# PCB_RTM_Loopback.net
KiCad netlist of a schematic drawn in Altium Designer
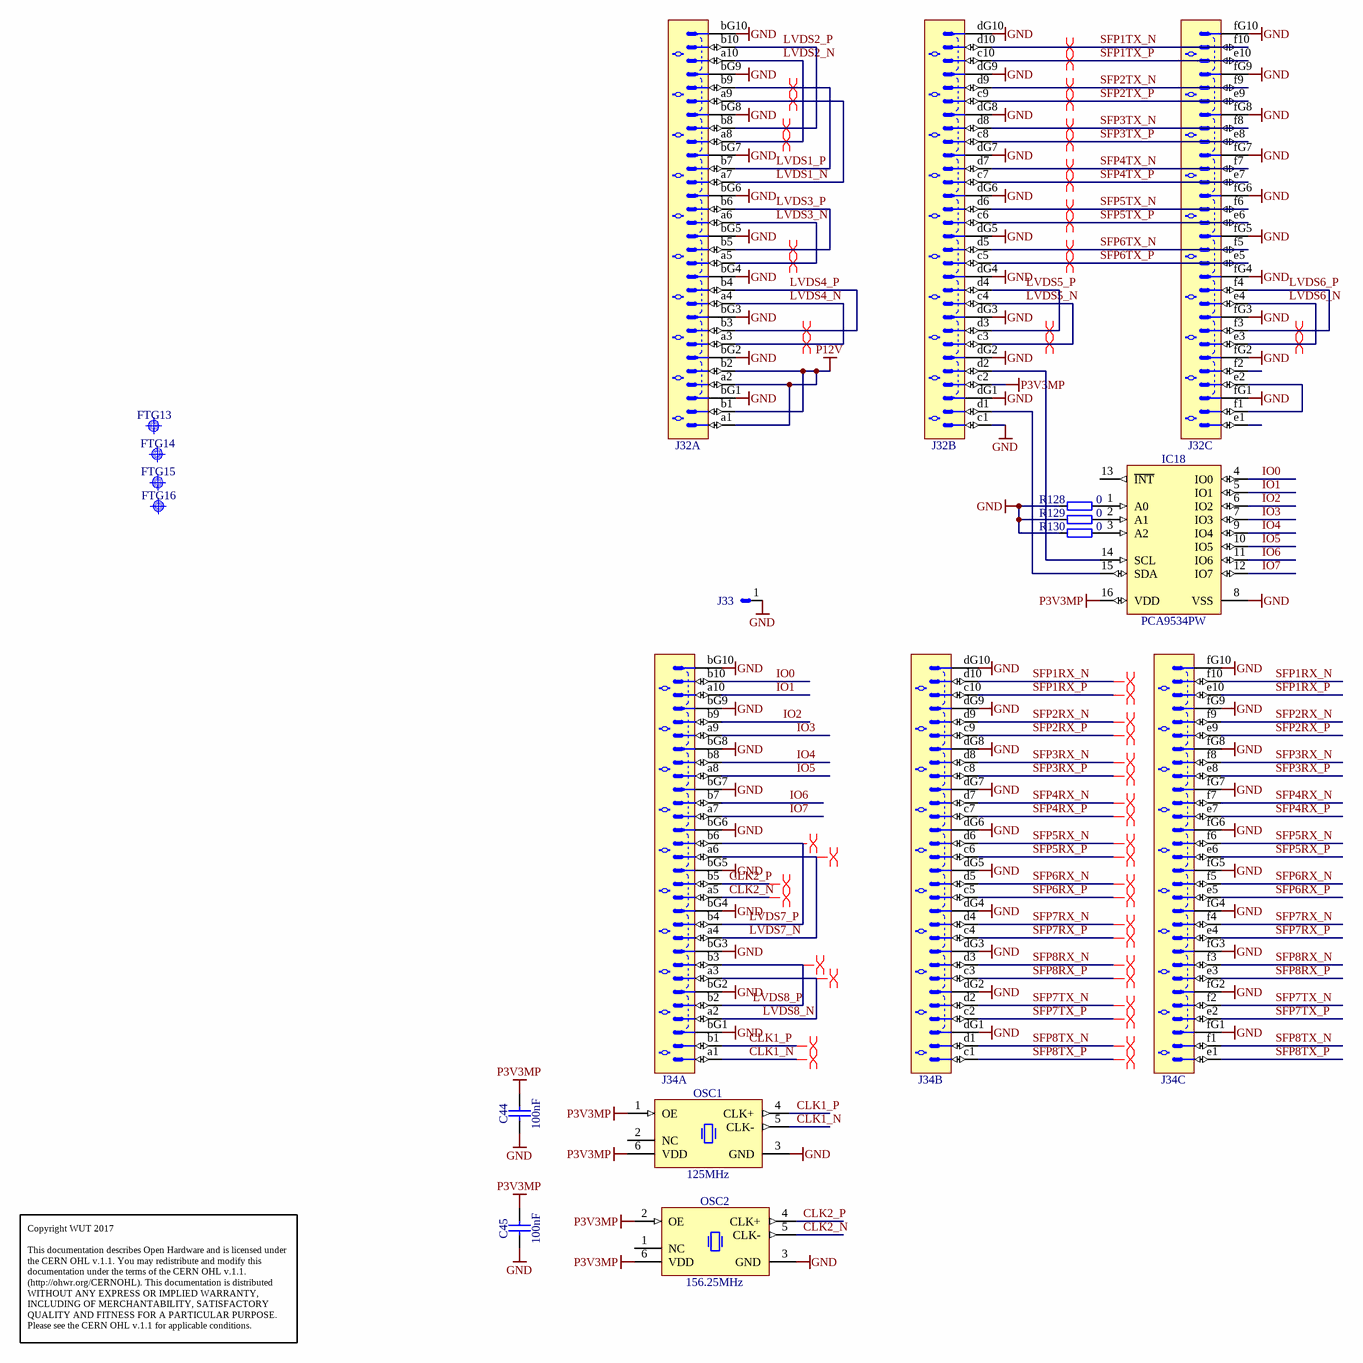
[diagram p0: PCB_RTM_Loopback.SchDoc]

(export (version "E")
  (design (tool "Eeschema 10.0.6"))
  (components
    (comp (ref "C44")
      (value "100nF")
      (footprint "CAPC1005X55N")
      (description "Non-polarised capacitor")
      (fields
        (field (name "PART NUMBER") "CC0402_100NF_16V_10%_X7R")
        (field (name "VOLTAGE") "16V")
        (field (name "AUTHOR") "CERN DEM JLC")
      )
      (libsource (lib "Capacitors") (part "Capacitor - non polarized"))
    )
    (comp (ref "C45")
      (value "100nF")
      (footprint "CAPC1005X55N")
      (description "Non-polarised capacitor")
      (fields
        (field (name "PART NUMBER") "CC0402_100NF_16V_10%_X7R")
        (field (name "VOLTAGE") "16V")
        (field (name "AUTHOR") "CERN DEM JLC")
      )
      (libsource (lib "Capacitors") (part "Capacitor - non polarized"))
    )
    (comp (ref "FTG13")
      (value "Use only in PCB")
      (footprint "FIDUCIAL_TOP_C100-200")
      (description "Fiducial Target")
      (fields (field (name "PART NUMBER") "FIDUCIAL_TARGET_C100-200") (field (name "AUTHOR") "CERN DEM JLC"))
      (libsource (lib "Eletro-mechanical") (part "Fiducial Target"))
    )
    (comp (ref "FTG14")
      (value "Use only in PCB")
      (footprint "FIDUCIAL_TOP_S100-200")
      (description "Fiducial Target")
      (fields (field (name "PART NUMBER") "FIDUCIAL_TARGET_S100-200") (field (name "AUTHOR") "CERN DEM JLC"))
      (libsource (lib "Eletro-mechanical") (part "Fiducial Target"))
    )
    (comp (ref "FTG15")
      (value "Use only in PCB")
      (footprint "FIDUCIAL_TOP_S200-400")
      (description "Fiducial Target")
      (fields (field (name "PART NUMBER") "FIDUCIAL_TARGET_S200-400") (field (name "AUTHOR") "CERN DEM JLC"))
      (libsource (lib "Eletro-mechanical") (part "Fiducial Target"))
    )
    (comp (ref "FTG16")
      (value "Use only in PCB")
      (footprint "FIDUCIAL_TOP_S100-200")
      (description "Fiducial Target")
      (fields (field (name "PART NUMBER") "FIDUCIAL_TARGET_S100-200") (field (name "AUTHOR") "CERN DEM JLC"))
      (libsource (lib "Eletro-mechanical") (part "Fiducial Target"))
    )
    (comp (ref "IC18")
      (value "PCA9534PW")
      (footprint "SOP65P640X110-16N")
      (description "8-Bit I2C-Bus and SMBus Low Power I/O Port with Interrupt")
      (fields (field (name "MANUFACTURER") "ANALOG DEVICES") (field (name "AUTHOR") "CERN DEM JLC"))
      (libsource (lib "ICs And Semiconductors") (part "PCA9534PW"))
    )
    (comp (ref "J32")
      (value "~")
      (footprint "TYCO_6469183-1")
      (description "Connector 60 ATCA Male 30 Pairs (60 Signals) + 3x10 Ground")
      (fields (field (name "PART NUMBER") "TYCO_6469183-1"))
      (libsource (lib "Connectors") (part "Connector ATCA 60+30 Male"))
    )
    (comp (ref "J33")
      (value "~")
      (footprint "TYCO_1469265-1")
      (description "Single Pin Male")
      (fields (field (name "PART NUMBER") "TYCO_1469265-1"))
      (libsource (lib "Connectors") (part "Single Pin Male"))
    )
    (comp (ref "J34")
      (value "~")
      (footprint "TYCO_6469183-1")
      (description "Connector 60 ATCA Male 30 Pairs (60 Signals) + 3x10 Ground")
      (fields (field (name "PART NUMBER") "TYCO_6469183-1"))
      (libsource (lib "Connectors") (part "Connector ATCA 60+30 Male"))
    )
    (comp (ref "OSC1")
      (value "125MHz")
      (footprint "OSC_SILICON-LAB_SI531")
      (description "10-1400MHz, Crystal Oscillator (XO), Si531 Series")
      (fields
        (field (name "PART NUMBER") "OSC_125MHZ_SILICON-LAB_531BC125M000DG")
        (field (name "MANUFACTURER") "SILICON LABS")
        (field (name "AUTHOR") "CERN DEM MR")
      )
      (libsource (lib "ICs And Semiconductors") (part "Oscillator SILICON-LAB_Si531"))
    )
    (comp (ref "OSC2")
      (value "156.25MHz")
      (footprint "OSC_SILICON-LAB_SI530")
      (description "10-1400MHz, Crystal Oscillator (XO), Si530 Series")
      (fields
        (field (name "PART NUMBER") "OSC_156.25MHZ_SILICON-LAB_530BC156M250DG")
        (field (name "MANUFACTURER") "SILICON LABS")
        (field (name "AUTHOR") "CERN DEM MR")
      )
      (libsource (lib "ICs And Semiconductors") (part "Oscillator SILICON-LAB_Si530_a"))
    )
    (comp (ref "R128")
      (value "0")
      (footprint "RESC1005X40N")
      (description "Resistor")
      (fields
        (field (name "PART NUMBER") "R0402_0R_JUMPER")
        (field (name "MANUFACTURER") "GENERIC")
        (field (name "AUTHOR") "CERN DEM JLC")
      )
      (libsource (lib "Resistors") (part "Resistor"))
    )
    (comp (ref "R129")
      (value "0")
      (footprint "RESC1005X40N")
      (description "Resistor")
      (fields
        (field (name "PART NUMBER") "R0402_0R_JUMPER")
        (field (name "MANUFACTURER") "GENERIC")
        (field (name "AUTHOR") "CERN DEM JLC")
      )
      (libsource (lib "Resistors") (part "Resistor"))
    )
    (comp (ref "R130")
      (value "0")
      (footprint "RESC1005X40N")
      (description "Resistor")
      (fields
        (field (name "PART NUMBER") "R0402_0R_JUMPER")
        (field (name "MANUFACTURER") "GENERIC")
        (field (name "AUTHOR") "CERN DEM JLC")
      )
      (libsource (lib "Resistors") (part "Resistor"))
    )
  )
  (nets
    (net (code "1") (name "/CLK1_N") (class "Default")
      (node (ref "J34") (pin "a1") (pinfunction "a1_a1") (pintype "bidirectional"))
      (node (ref "OSC1") (pin "5") (pinfunction "CLK-_5") (pintype "output"))
    )
    (net (code "2") (name "/CLK1_P") (class "Default")
      (node (ref "J34") (pin "b1") (pinfunction "b1_b1") (pintype "bidirectional"))
      (node (ref "OSC1") (pin "4") (pinfunction "CLK+_4") (pintype "output"))
    )
    (net (code "3") (name "/CLK2_N") (class "Default")
      (node (ref "J34") (pin "a5") (pinfunction "a5_a5") (pintype "bidirectional"))
      (node (ref "OSC2") (pin "5") (pinfunction "CLK-_5") (pintype "output"))
    )
    (net (code "4") (name "/CLK2_P") (class "Default")
      (node (ref "J34") (pin "b5") (pinfunction "b5_b5") (pintype "bidirectional"))
      (node (ref "OSC2") (pin "4") (pinfunction "CLK+_4") (pintype "output"))
    )
    (net (code "5") (name "/IO0") (class "Default")
      (node (ref "IC18") (pin "4") (pinfunction "IO0_4") (pintype "bidirectional"))
      (node (ref "J34") (pin "b10") (pinfunction "b10_b10") (pintype "bidirectional"))
    )
    (net (code "6") (name "/IO1") (class "Default")
      (node (ref "IC18") (pin "5") (pinfunction "IO1_5") (pintype "bidirectional"))
      (node (ref "J34") (pin "a10") (pinfunction "a10_a10") (pintype "bidirectional"))
    )
    (net (code "7") (name "/IO2") (class "Default")
      (node (ref "IC18") (pin "6") (pinfunction "IO2_6") (pintype "bidirectional"))
      (node (ref "J34") (pin "b9") (pinfunction "b9_b9") (pintype "bidirectional"))
    )
    (net (code "8") (name "/IO3") (class "Default")
      (node (ref "IC18") (pin "7") (pinfunction "IO3_7") (pintype "bidirectional"))
      (node (ref "J34") (pin "a9") (pinfunction "a9_a9") (pintype "bidirectional"))
    )
    (net (code "9") (name "/IO4") (class "Default")
      (node (ref "IC18") (pin "9") (pinfunction "IO4_9") (pintype "bidirectional"))
      (node (ref "J34") (pin "b8") (pinfunction "b8_b8") (pintype "bidirectional"))
    )
    (net (code "10") (name "/IO5") (class "Default")
      (node (ref "IC18") (pin "10") (pinfunction "IO5_10") (pintype "bidirectional"))
      (node (ref "J34") (pin "a8") (pinfunction "a8_a8") (pintype "bidirectional"))
    )
    (net (code "11") (name "/IO6") (class "Default")
      (node (ref "IC18") (pin "11") (pinfunction "IO6_11") (pintype "bidirectional"))
      (node (ref "J34") (pin "b7") (pinfunction "b7_b7") (pintype "bidirectional"))
    )
    (net (code "12") (name "/IO7") (class "Default")
      (node (ref "IC18") (pin "12") (pinfunction "IO7_12") (pintype "bidirectional"))
      (node (ref "J34") (pin "a7") (pinfunction "a7_a7") (pintype "bidirectional"))
    )
    (net (code "13") (name "/LVDS1_N") (class "Default")
      (node (ref "J32") (pin "a7") (pinfunction "a7_a7") (pintype "bidirectional"))
      (node (ref "J32") (pin "a9") (pinfunction "a9_a9") (pintype "bidirectional"))
    )
    (net (code "14") (name "/LVDS1_P") (class "Default")
      (node (ref "J32") (pin "b7") (pinfunction "b7_b7") (pintype "bidirectional"))
      (node (ref "J32") (pin "b9") (pinfunction "b9_b9") (pintype "bidirectional"))
    )
    (net (code "15") (name "/LVDS2_N") (class "Default")
      (node (ref "J32") (pin "a10") (pinfunction "a10_a10") (pintype "bidirectional"))
      (node (ref "J32") (pin "a8") (pinfunction "a8_a8") (pintype "bidirectional"))
    )
    (net (code "16") (name "/LVDS2_P") (class "Default")
      (node (ref "J32") (pin "b10") (pinfunction "b10_b10") (pintype "bidirectional"))
      (node (ref "J32") (pin "b8") (pinfunction "b8_b8") (pintype "bidirectional"))
    )
    (net (code "17") (name "/LVDS3_N") (class "Default")
      (node (ref "J32") (pin "a5") (pinfunction "a5_a5") (pintype "bidirectional"))
      (node (ref "J32") (pin "a6") (pinfunction "a6_a6") (pintype "bidirectional"))
    )
    (net (code "18") (name "/LVDS3_P") (class "Default")
      (node (ref "J32") (pin "b5") (pinfunction "b5_b5") (pintype "bidirectional"))
      (node (ref "J32") (pin "b6") (pinfunction "b6_b6") (pintype "bidirectional"))
    )
    (net (code "19") (name "/LVDS4_N") (class "Default")
      (node (ref "J32") (pin "a3") (pinfunction "a3_a3") (pintype "bidirectional"))
      (node (ref "J32") (pin "a4") (pinfunction "a4_a4") (pintype "bidirectional"))
    )
    (net (code "20") (name "/LVDS4_P") (class "Default")
      (node (ref "J32") (pin "b3") (pinfunction "b3_b3") (pintype "bidirectional"))
      (node (ref "J32") (pin "b4") (pinfunction "b4_b4") (pintype "bidirectional"))
    )
    (net (code "21") (name "/LVDS5_N") (class "Default")
      (node (ref "J32") (pin "c3") (pinfunction "c3_c3") (pintype "bidirectional"))
      (node (ref "J32") (pin "c4") (pinfunction "c4_c4") (pintype "bidirectional"))
    )
    (net (code "22") (name "/LVDS5_P") (class "Default")
      (node (ref "J32") (pin "d3") (pinfunction "d3_d3") (pintype "bidirectional"))
      (node (ref "J32") (pin "d4") (pinfunction "d4_d4") (pintype "bidirectional"))
    )
    (net (code "23") (name "/LVDS6_N") (class "Default")
      (node (ref "J32") (pin "e3") (pinfunction "e3_e3") (pintype "bidirectional"))
      (node (ref "J32") (pin "e4") (pinfunction "e4_e4") (pintype "bidirectional"))
    )
    (net (code "24") (name "/LVDS6_P") (class "Default")
      (node (ref "J32") (pin "f3") (pinfunction "f3_f3") (pintype "bidirectional"))
      (node (ref "J32") (pin "f4") (pinfunction "f4_f4") (pintype "bidirectional"))
    )
    (net (code "25") (name "/LVDS7_N") (class "Default")
      (node (ref "J34") (pin "a4") (pinfunction "a4_a4") (pintype "bidirectional"))
      (node (ref "J34") (pin "a6") (pinfunction "a6_a6") (pintype "bidirectional"))
    )
    (net (code "26") (name "/LVDS7_P") (class "Default")
      (node (ref "J34") (pin "b4") (pinfunction "b4_b4") (pintype "bidirectional"))
      (node (ref "J34") (pin "b6") (pinfunction "b6_b6") (pintype "bidirectional"))
    )
    (net (code "27") (name "/LVDS8_N") (class "Default")
      (node (ref "J34") (pin "a2") (pinfunction "a2_a2") (pintype "bidirectional"))
      (node (ref "J34") (pin "a3") (pinfunction "a3_a3") (pintype "bidirectional"))
    )
    (net (code "28") (name "/LVDS8_P") (class "Default")
      (node (ref "J34") (pin "b2") (pinfunction "b2_b2") (pintype "bidirectional"))
      (node (ref "J34") (pin "b3") (pinfunction "b3_b3") (pintype "bidirectional"))
    )
    (net (code "29") (name "/SFP1RX_N") (class "Default")
      (node (ref "J34") (pin "d10") (pinfunction "d10_d10") (pintype "bidirectional"))
      (node (ref "J34") (pin "f10") (pinfunction "f10_f10") (pintype "bidirectional"))
    )
    (net (code "30") (name "/SFP1RX_P") (class "Default")
      (node (ref "J34") (pin "c10") (pinfunction "c10_c10") (pintype "bidirectional"))
      (node (ref "J34") (pin "e10") (pinfunction "e10_e10") (pintype "bidirectional"))
    )
    (net (code "31") (name "/SFP1TX_N") (class "Default")
      (node (ref "J32") (pin "d10") (pinfunction "d10_d10") (pintype "bidirectional"))
      (node (ref "J32") (pin "f10") (pinfunction "f10_f10") (pintype "bidirectional"))
    )
    (net (code "32") (name "/SFP1TX_P") (class "Default")
      (node (ref "J32") (pin "c10") (pinfunction "c10_c10") (pintype "bidirectional"))
      (node (ref "J32") (pin "e10") (pinfunction "e10_e10") (pintype "bidirectional"))
    )
    (net (code "33") (name "/SFP2RX_N") (class "Default")
      (node (ref "J34") (pin "d9") (pinfunction "d9_d9") (pintype "bidirectional"))
      (node (ref "J34") (pin "f9") (pinfunction "f9_f9") (pintype "bidirectional"))
    )
    (net (code "34") (name "/SFP2RX_P") (class "Default")
      (node (ref "J34") (pin "c9") (pinfunction "c9_c9") (pintype "bidirectional"))
      (node (ref "J34") (pin "e9") (pinfunction "e9_e9") (pintype "bidirectional"))
    )
    (net (code "35") (name "/SFP2TX_N") (class "Default")
      (node (ref "J32") (pin "d9") (pinfunction "d9_d9") (pintype "bidirectional"))
      (node (ref "J32") (pin "f9") (pinfunction "f9_f9") (pintype "bidirectional"))
    )
    (net (code "36") (name "/SFP2TX_P") (class "Default")
      (node (ref "J32") (pin "c9") (pinfunction "c9_c9") (pintype "bidirectional"))
      (node (ref "J32") (pin "e9") (pinfunction "e9_e9") (pintype "bidirectional"))
    )
    (net (code "37") (name "/SFP3RX_N") (class "Default")
      (node (ref "J34") (pin "d8") (pinfunction "d8_d8") (pintype "bidirectional"))
      (node (ref "J34") (pin "f8") (pinfunction "f8_f8") (pintype "bidirectional"))
    )
    (net (code "38") (name "/SFP3RX_P") (class "Default")
      (node (ref "J34") (pin "c8") (pinfunction "c8_c8") (pintype "bidirectional"))
      (node (ref "J34") (pin "e8") (pinfunction "e8_e8") (pintype "bidirectional"))
    )
    (net (code "39") (name "/SFP3TX_N") (class "Default")
      (node (ref "J32") (pin "d8") (pinfunction "d8_d8") (pintype "bidirectional"))
      (node (ref "J32") (pin "f8") (pinfunction "f8_f8") (pintype "bidirectional"))
    )
    (net (code "40") (name "/SFP3TX_P") (class "Default")
      (node (ref "J32") (pin "c8") (pinfunction "c8_c8") (pintype "bidirectional"))
      (node (ref "J32") (pin "e8") (pinfunction "e8_e8") (pintype "bidirectional"))
    )
    (net (code "41") (name "/SFP4RX_N") (class "Default")
      (node (ref "J34") (pin "d7") (pinfunction "d7_d7") (pintype "bidirectional"))
      (node (ref "J34") (pin "f7") (pinfunction "f7_f7") (pintype "bidirectional"))
    )
    (net (code "42") (name "/SFP4RX_P") (class "Default")
      (node (ref "J34") (pin "c7") (pinfunction "c7_c7") (pintype "bidirectional"))
      (node (ref "J34") (pin "e7") (pinfunction "e7_e7") (pintype "bidirectional"))
    )
    (net (code "43") (name "/SFP4TX_N") (class "Default")
      (node (ref "J32") (pin "d7") (pinfunction "d7_d7") (pintype "bidirectional"))
      (node (ref "J32") (pin "f7") (pinfunction "f7_f7") (pintype "bidirectional"))
    )
    (net (code "44") (name "/SFP4TX_P") (class "Default")
      (node (ref "J32") (pin "c7") (pinfunction "c7_c7") (pintype "bidirectional"))
      (node (ref "J32") (pin "e7") (pinfunction "e7_e7") (pintype "bidirectional"))
    )
    (net (code "45") (name "/SFP5RX_N") (class "Default")
      (node (ref "J34") (pin "d6") (pinfunction "d6_d6") (pintype "bidirectional"))
      (node (ref "J34") (pin "f6") (pinfunction "f6_f6") (pintype "bidirectional"))
    )
    (net (code "46") (name "/SFP5RX_P") (class "Default")
      (node (ref "J34") (pin "c6") (pinfunction "c6_c6") (pintype "bidirectional"))
      (node (ref "J34") (pin "e6") (pinfunction "e6_e6") (pintype "bidirectional"))
    )
    (net (code "47") (name "/SFP5TX_N") (class "Default")
      (node (ref "J32") (pin "d6") (pinfunction "d6_d6") (pintype "bidirectional"))
      (node (ref "J32") (pin "f6") (pinfunction "f6_f6") (pintype "bidirectional"))
    )
    (net (code "48") (name "/SFP5TX_P") (class "Default")
      (node (ref "J32") (pin "c6") (pinfunction "c6_c6") (pintype "bidirectional"))
      (node (ref "J32") (pin "e6") (pinfunction "e6_e6") (pintype "bidirectional"))
    )
    (net (code "49") (name "/SFP6RX_N") (class "Default")
      (node (ref "J34") (pin "d5") (pinfunction "d5_d5") (pintype "bidirectional"))
      (node (ref "J34") (pin "f5") (pinfunction "f5_f5") (pintype "bidirectional"))
    )
    (net (code "50") (name "/SFP6RX_P") (class "Default")
      (node (ref "J34") (pin "c5") (pinfunction "c5_c5") (pintype "bidirectional"))
      (node (ref "J34") (pin "e5") (pinfunction "e5_e5") (pintype "bidirectional"))
    )
    (net (code "51") (name "/SFP6TX_N") (class "Default")
      (node (ref "J32") (pin "d5") (pinfunction "d5_d5") (pintype "bidirectional"))
      (node (ref "J32") (pin "f5") (pinfunction "f5_f5") (pintype "bidirectional"))
    )
    (net (code "52") (name "/SFP6TX_P") (class "Default")
      (node (ref "J32") (pin "c5") (pinfunction "c5_c5") (pintype "bidirectional"))
      (node (ref "J32") (pin "e5") (pinfunction "e5_e5") (pintype "bidirectional"))
    )
    (net (code "53") (name "/SFP7RX_N") (class "Default")
      (node (ref "J34") (pin "d4") (pinfunction "d4_d4") (pintype "bidirectional"))
      (node (ref "J34") (pin "f4") (pinfunction "f4_f4") (pintype "bidirectional"))
    )
    (net (code "54") (name "/SFP7RX_P") (class "Default")
      (node (ref "J34") (pin "c4") (pinfunction "c4_c4") (pintype "bidirectional"))
      (node (ref "J34") (pin "e4") (pinfunction "e4_e4") (pintype "bidirectional"))
    )
    (net (code "55") (name "/SFP7TX_N") (class "Default")
      (node (ref "J34") (pin "d2") (pinfunction "d2_d2") (pintype "bidirectional"))
      (node (ref "J34") (pin "f2") (pinfunction "f2_f2") (pintype "bidirectional"))
    )
    (net (code "56") (name "/SFP7TX_P") (class "Default")
      (node (ref "J34") (pin "c2") (pinfunction "c2_c2") (pintype "bidirectional"))
      (node (ref "J34") (pin "e2") (pinfunction "e2_e2") (pintype "bidirectional"))
    )
    (net (code "57") (name "/SFP8RX_N") (class "Default")
      (node (ref "J34") (pin "d3") (pinfunction "d3_d3") (pintype "bidirectional"))
      (node (ref "J34") (pin "f3") (pinfunction "f3_f3") (pintype "bidirectional"))
    )
    (net (code "58") (name "/SFP8RX_P") (class "Default")
      (node (ref "J34") (pin "c3") (pinfunction "c3_c3") (pintype "bidirectional"))
      (node (ref "J34") (pin "e3") (pinfunction "e3_e3") (pintype "bidirectional"))
    )
    (net (code "59") (name "/SFP8TX_N") (class "Default")
      (node (ref "J34") (pin "d1") (pinfunction "d1_d1") (pintype "bidirectional"))
      (node (ref "J34") (pin "f1") (pinfunction "f1_f1") (pintype "bidirectional"))
    )
    (net (code "60") (name "/SFP8TX_P") (class "Default")
      (node (ref "J34") (pin "c1") (pinfunction "c1_c1") (pintype "bidirectional"))
      (node (ref "J34") (pin "e1") (pinfunction "e1_e1") (pintype "bidirectional"))
    )
    (net (code "61") (name "GND") (class "Default")
      (node (ref "C44") (pin "1") (pinfunction "1_1") (pintype "passive"))
      (node (ref "C45") (pin "1") (pinfunction "1_1") (pintype "passive"))
      (node (ref "IC18") (pin "8") (pinfunction "VSS_8") (pintype "power_in"))
      (node (ref "J32") (pin "bG1") (pinfunction "bG1_bG1") (pintype "power_in"))
      (node (ref "J32") (pin "bG10") (pinfunction "bG10_bG10") (pintype "power_in"))
      (node (ref "J32") (pin "bG2") (pinfunction "bG2_bG2") (pintype "power_in"))
      (node (ref "J32") (pin "bG3") (pinfunction "bG3_bG3") (pintype "power_in"))
      (node (ref "J32") (pin "bG4") (pinfunction "bG4_bG4") (pintype "power_in"))
      (node (ref "J32") (pin "bG5") (pinfunction "bG5_bG5") (pintype "power_in"))
      (node (ref "J32") (pin "bG6") (pinfunction "bG6_bG6") (pintype "power_in"))
      (node (ref "J32") (pin "bG7") (pinfunction "bG7_bG7") (pintype "power_in"))
      (node (ref "J32") (pin "bG8") (pinfunction "bG8_bG8") (pintype "power_in"))
      (node (ref "J32") (pin "bG9") (pinfunction "bG9_bG9") (pintype "power_in"))
      (node (ref "J32") (pin "c1") (pinfunction "c1_c1") (pintype "bidirectional"))
      (node (ref "J32") (pin "dG1") (pinfunction "dG1_dG1") (pintype "power_in"))
      (node (ref "J32") (pin "dG10") (pinfunction "dG10_dG10") (pintype "power_in"))
      (node (ref "J32") (pin "dG2") (pinfunction "dG2_dG2") (pintype "power_in"))
      (node (ref "J32") (pin "dG3") (pinfunction "dG3_dG3") (pintype "power_in"))
      (node (ref "J32") (pin "dG4") (pinfunction "dG4_dG4") (pintype "power_in"))
      (node (ref "J32") (pin "dG5") (pinfunction "dG5_dG5") (pintype "power_in"))
      (node (ref "J32") (pin "dG6") (pinfunction "dG6_dG6") (pintype "power_in"))
      (node (ref "J32") (pin "dG7") (pinfunction "dG7_dG7") (pintype "power_in"))
      (node (ref "J32") (pin "dG8") (pinfunction "dG8_dG8") (pintype "power_in"))
      (node (ref "J32") (pin "dG9") (pinfunction "dG9_dG9") (pintype "power_in"))
      (node (ref "J32") (pin "fG1") (pinfunction "fG1_fG1") (pintype "power_in"))
      (node (ref "J32") (pin "fG10") (pinfunction "fG10_fG10") (pintype "power_in"))
      (node (ref "J32") (pin "fG2") (pinfunction "fG2_fG2") (pintype "power_in"))
      (node (ref "J32") (pin "fG3") (pinfunction "fG3_fG3") (pintype "power_in"))
      (node (ref "J32") (pin "fG4") (pinfunction "fG4_fG4") (pintype "power_in"))
      (node (ref "J32") (pin "fG5") (pinfunction "fG5_fG5") (pintype "power_in"))
      (node (ref "J32") (pin "fG6") (pinfunction "fG6_fG6") (pintype "power_in"))
      (node (ref "J32") (pin "fG7") (pinfunction "fG7_fG7") (pintype "power_in"))
      (node (ref "J32") (pin "fG8") (pinfunction "fG8_fG8") (pintype "power_in"))
      (node (ref "J32") (pin "fG9") (pinfunction "fG9_fG9") (pintype "power_in"))
      (node (ref "J33") (pin "1") (pinfunction "1_1") (pintype "bidirectional"))
      (node (ref "J34") (pin "bG1") (pinfunction "bG1_bG1") (pintype "power_in"))
      (node (ref "J34") (pin "bG10") (pinfunction "bG10_bG10") (pintype "power_in"))
      (node (ref "J34") (pin "bG2") (pinfunction "bG2_bG2") (pintype "power_in"))
      (node (ref "J34") (pin "bG3") (pinfunction "bG3_bG3") (pintype "power_in"))
      (node (ref "J34") (pin "bG4") (pinfunction "bG4_bG4") (pintype "power_in"))
      (node (ref "J34") (pin "bG5") (pinfunction "bG5_bG5") (pintype "power_in"))
      (node (ref "J34") (pin "bG6") (pinfunction "bG6_bG6") (pintype "power_in"))
      (node (ref "J34") (pin "bG7") (pinfunction "bG7_bG7") (pintype "power_in"))
      (node (ref "J34") (pin "bG8") (pinfunction "bG8_bG8") (pintype "power_in"))
      (node (ref "J34") (pin "bG9") (pinfunction "bG9_bG9") (pintype "power_in"))
      (node (ref "J34") (pin "dG1") (pinfunction "dG1_dG1") (pintype "power_in"))
      (node (ref "J34") (pin "dG10") (pinfunction "dG10_dG10") (pintype "power_in"))
      (node (ref "J34") (pin "dG2") (pinfunction "dG2_dG2") (pintype "power_in"))
      (node (ref "J34") (pin "dG3") (pinfunction "dG3_dG3") (pintype "power_in"))
      (node (ref "J34") (pin "dG4") (pinfunction "dG4_dG4") (pintype "power_in"))
      (node (ref "J34") (pin "dG5") (pinfunction "dG5_dG5") (pintype "power_in"))
      (node (ref "J34") (pin "dG6") (pinfunction "dG6_dG6") (pintype "power_in"))
      (node (ref "J34") (pin "dG7") (pinfunction "dG7_dG7") (pintype "power_in"))
      (node (ref "J34") (pin "dG8") (pinfunction "dG8_dG8") (pintype "power_in"))
      (node (ref "J34") (pin "dG9") (pinfunction "dG9_dG9") (pintype "power_in"))
      (node (ref "J34") (pin "fG1") (pinfunction "fG1_fG1") (pintype "power_in"))
      (node (ref "J34") (pin "fG10") (pinfunction "fG10_fG10") (pintype "power_in"))
      (node (ref "J34") (pin "fG2") (pinfunction "fG2_fG2") (pintype "power_in"))
      (node (ref "J34") (pin "fG3") (pinfunction "fG3_fG3") (pintype "power_in"))
      (node (ref "J34") (pin "fG4") (pinfunction "fG4_fG4") (pintype "power_in"))
      (node (ref "J34") (pin "fG5") (pinfunction "fG5_fG5") (pintype "power_in"))
      (node (ref "J34") (pin "fG6") (pinfunction "fG6_fG6") (pintype "power_in"))
      (node (ref "J34") (pin "fG7") (pinfunction "fG7_fG7") (pintype "power_in"))
      (node (ref "J34") (pin "fG8") (pinfunction "fG8_fG8") (pintype "power_in"))
      (node (ref "J34") (pin "fG9") (pinfunction "fG9_fG9") (pintype "power_in"))
      (node (ref "OSC1") (pin "3") (pinfunction "GND_3") (pintype "power_in"))
      (node (ref "OSC2") (pin "3") (pinfunction "GND_3") (pintype "power_in"))
      (node (ref "R128") (pin "1") (pinfunction "1_1") (pintype "passive"))
      (node (ref "R129") (pin "1") (pinfunction "1_1") (pintype "passive"))
      (node (ref "R130") (pin "1") (pinfunction "1_1") (pintype "passive"))
    )
    (net (code "62") (name "Net-(IC18-A0)") (class "Default")
      (node (ref "IC18") (pin "1") (pinfunction "A0_1") (pintype "input"))
      (node (ref "R128") (pin "2") (pinfunction "2_2") (pintype "passive"))
    )
    (net (code "63") (name "Net-(IC18-A1)") (class "Default")
      (node (ref "IC18") (pin "2") (pinfunction "A1_2") (pintype "input"))
      (node (ref "R129") (pin "2") (pinfunction "2_2") (pintype "passive"))
    )
    (net (code "64") (name "Net-(IC18-A2)") (class "Default")
      (node (ref "IC18") (pin "3") (pinfunction "A2_3") (pintype "input"))
      (node (ref "R130") (pin "2") (pinfunction "2_2") (pintype "passive"))
    )
    (net (code "65") (name "Net-(IC18-SCL)") (class "Default")
      (node (ref "IC18") (pin "14") (pinfunction "SCL_14") (pintype "input"))
      (node (ref "J32") (pin "d2") (pinfunction "d2_d2") (pintype "bidirectional"))
    )
    (net (code "66") (name "Net-(IC18-SDA)") (class "Default")
      (node (ref "IC18") (pin "15") (pinfunction "SDA_15") (pintype "bidirectional"))
      (node (ref "J32") (pin "d1") (pinfunction "d1_d1") (pintype "bidirectional"))
    )
    (net (code "67") (name "Net-(J32-Pade2)") (class "Default")
      (node (ref "J32") (pin "e2") (pinfunction "e2_e2") (pintype "bidirectional"))
      (node (ref "J32") (pin "f1") (pinfunction "f1_f1") (pintype "bidirectional"))
    )
    (net (code "68") (name "P3V3MP") (class "Default")
      (node (ref "C44") (pin "2") (pinfunction "2_2") (pintype "passive"))
      (node (ref "C45") (pin "2") (pinfunction "2_2") (pintype "passive"))
      (node (ref "IC18") (pin "16") (pinfunction "VDD_16") (pintype "bidirectional"))
      (node (ref "J32") (pin "c2") (pinfunction "c2_c2") (pintype "bidirectional"))
      (node (ref "OSC1") (pin "1") (pinfunction "OE_1") (pintype "input"))
      (node (ref "OSC1") (pin "6") (pinfunction "VDD_6") (pintype "power_in"))
      (node (ref "OSC2") (pin "2") (pinfunction "OE_2") (pintype "input"))
      (node (ref "OSC2") (pin "6") (pinfunction "VDD_6") (pintype "power_in"))
    )
    (net (code "69") (name "P12V") (class "Default")
      (node (ref "J32") (pin "a1") (pinfunction "a1_a1") (pintype "bidirectional"))
      (node (ref "J32") (pin "a2") (pinfunction "a2_a2") (pintype "bidirectional"))
      (node (ref "J32") (pin "b1") (pinfunction "b1_b1") (pintype "bidirectional"))
      (node (ref "J32") (pin "b2") (pinfunction "b2_b2") (pintype "bidirectional"))
    )
    (net (code "70") (name "unconnected-(IC18-~{INT}-Pad13)") (class "Default")
      (node (ref "IC18") (pin "13") (pinfunction "~{INT}_13") (pintype "output"))
    )
    (net (code "71") (name "unconnected-(J32-Pade1)") (class "Default")
      (node (ref "J32") (pin "e1") (pinfunction "e1_e1") (pintype "bidirectional"))
    )
    (net (code "72") (name "unconnected-(J32-Padf2)") (class "Default")
      (node (ref "J32") (pin "f2") (pinfunction "f2_f2") (pintype "bidirectional"))
    )
    (net (code "73") (name "unconnected-(OSC1-NC-Pad2)") (class "Default")
      (node (ref "OSC1") (pin "2") (pinfunction "NC_2") (pintype "passive"))
    )
    (net (code "74") (name "unconnected-(OSC2-NC-Pad1)") (class "Default")
      (node (ref "OSC2") (pin "1") (pinfunction "NC_1") (pintype "passive"))
    )
  )
)
